# BUCK_SCHEM.net
KiCad netlist of a schematic drawn in Altium Designer
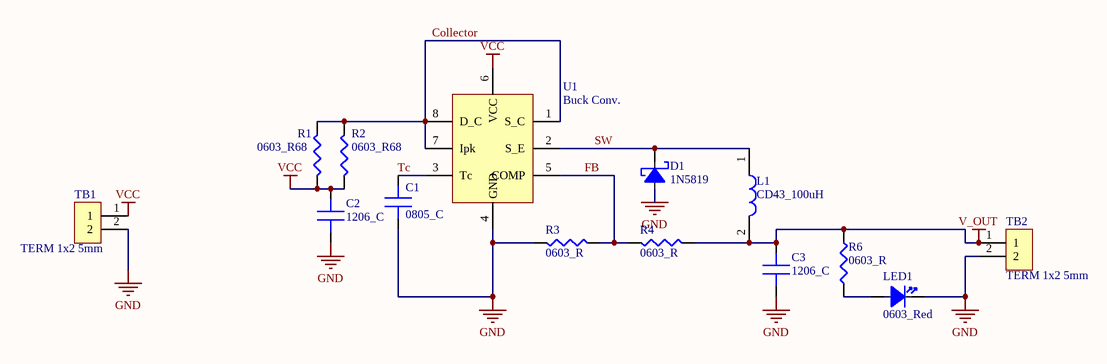
[diagram p0: BUCK_SCHEM.SchDoc]

(export (version "E")
  (design (tool "Eeschema 10.0.6"))
  (components
    (comp (ref "C1")
      (value "0805_C")
      (footprint "C0805 - 0.1uf")
      (description "0805 Capacitor")
      (libsource (lib "TimerSMD_Components") (part "0805 Capacitor"))
    )
    (comp (ref "C2")
      (value "1206_C")
      (footprint "1206")
      (description "1206 Capacitor")
      (libsource (lib "TimerSMD_Components") (part "1206 Capacitor"))
    )
    (comp (ref "C3")
      (value "1206_C")
      (footprint "1206")
      (description "1206 Capacitor")
      (libsource (lib "TimerSMD_Components") (part "1206 Capacitor"))
    )
    (comp (ref "D1")
      (value "1N5819")
      (footprint "D0-214AC")
      (description "1N5819 SS14 SMA Schottky Barrier Diodes (SBD) 40V 550mV@1A 1A")
      (libsource (lib "TimerSMD_Components") (part "1N5819"))
    )
    (comp (ref "L1")
      (value "CD43_100uH")
      (footprint "CD43")
      (libsource (lib "TimerSMD_Components") (part "100uH 4.5x4x3.2mm"))
    )
    (comp (ref "LED1")
      (value "0603_Red")
      (footprint "0603_LED")
      (libsource (lib "TimerSMD_Components") (part "0603LED"))
    )
    (comp (ref "R1")
      (value "0603_R68")
      (footprint "0603_CAP")
      (libsource (lib "TimerSMD_Components") (part "0603 Resistor"))
    )
    (comp (ref "R2")
      (value "0603_R68")
      (footprint "0603_CAP")
      (libsource (lib "TimerSMD_Components") (part "0603 Resistor"))
    )
    (comp (ref "R3")
      (value "0603_R")
      (footprint "0603_CAP")
      (libsource (lib "TimerSMD_Components") (part "0603 Resistor"))
    )
    (comp (ref "R4")
      (value "0603_R")
      (footprint "0603_CAP")
      (libsource (lib "TimerSMD_Components") (part "0603 Resistor"))
    )
    (comp (ref "R6")
      (value "0603_R")
      (footprint "0603_CAP")
      (libsource (lib "TimerSMD_Components") (part "0603 Resistor"))
    )
    (comp (ref "TB1")
      (value "TERM 1x2 5mm")
      (footprint "Terminal_5mm")
      (fields (field (name "VOLTAGE") "300V"))
      (libsource (lib "TimerSMD_Components") (part "Terminal BLK Green"))
    )
    (comp (ref "TB2")
      (value "TERM 1x2 5mm")
      (footprint "Terminal_5mm")
      (fields (field (name "VOLTAGE") "300V"))
      (libsource (lib "") (part "Terminal BLK Green_1"))
    )
    (comp (ref "U1")
      (value "Buck Conv.")
      (footprint "SOP8")
      (libsource (lib "TimerSMD_Components") (part "MC33063A"))
    )
  )
  (nets
    (net (code "1") (name "/Collector") (class "Default")
      (node (ref "R1") (pin "2") (pinfunction "2_2") (pintype "passive"))
      (node (ref "R2") (pin "2") (pinfunction "2_2") (pintype "passive"))
      (node (ref "U1") (pin "1") (pinfunction "S_C_1") (pintype "passive"))
      (node (ref "U1") (pin "7") (pinfunction "Ipk_7") (pintype "passive"))
      (node (ref "U1") (pin "8") (pinfunction "D_C_8") (pintype "passive"))
    )
    (net (code "2") (name "/FB") (class "Default")
      (node (ref "R3") (pin "2") (pinfunction "2_2") (pintype "passive"))
      (node (ref "R4") (pin "1") (pinfunction "1_1") (pintype "passive"))
      (node (ref "U1") (pin "5") (pinfunction "COMP_5") (pintype "passive"))
    )
    (net (code "3") (name "/SW") (class "Default")
      (node (ref "D1") (pin "K") (pinfunction "Cathode_K") (pintype "passive"))
      (node (ref "L1") (pin "1") (pinfunction "1_1") (pintype "passive"))
      (node (ref "U1") (pin "2") (pinfunction "S_E_2") (pintype "passive"))
    )
    (net (code "4") (name "/Tc") (class "Default")
      (node (ref "C1") (pin "2") (pinfunction "2_2") (pintype "passive"))
      (node (ref "U1") (pin "3") (pinfunction "Tc_3") (pintype "passive"))
    )
    (net (code "5") (name "GND") (class "Default")
      (node (ref "C1") (pin "1") (pinfunction "1_1") (pintype "passive"))
      (node (ref "C2") (pin "1") (pinfunction "1_1") (pintype "passive"))
      (node (ref "C3") (pin "1") (pinfunction "1_1") (pintype "passive"))
      (node (ref "D1") (pin "A") (pinfunction "Anode_A") (pintype "passive"))
      (node (ref "LED1") (pin "2") (pinfunction "Cathode_2") (pintype "passive"))
      (node (ref "R3") (pin "1") (pinfunction "1_1") (pintype "passive"))
      (node (ref "TB1") (pin "2") (pinfunction "2_2") (pintype "passive"))
      (node (ref "TB2") (pin "2") (pinfunction "2_2") (pintype "passive"))
      (node (ref "U1") (pin "4") (pinfunction "GND_4") (pintype "passive"))
    )
    (net (code "6") (name "Net-(LED1-Anode)") (class "Default")
      (node (ref "LED1") (pin "1") (pinfunction "Anode_1") (pintype "passive"))
      (node (ref "R6") (pin "1") (pinfunction "1_1") (pintype "passive"))
    )
    (net (code "7") (name "VCC") (class "Default")
      (node (ref "C2") (pin "2") (pinfunction "2_2") (pintype "passive"))
      (node (ref "R1") (pin "1") (pinfunction "1_1") (pintype "passive"))
      (node (ref "R2") (pin "1") (pinfunction "1_1") (pintype "passive"))
      (node (ref "TB1") (pin "1") (pinfunction "1_1") (pintype "passive"))
      (node (ref "U1") (pin "6") (pinfunction "VCC_6") (pintype "passive"))
    )
    (net (code "8") (name "V_OUT") (class "Default")
      (node (ref "C3") (pin "2") (pinfunction "2_2") (pintype "passive"))
      (node (ref "L1") (pin "2") (pinfunction "2_2") (pintype "passive"))
      (node (ref "R4") (pin "2") (pinfunction "2_2") (pintype "passive"))
      (node (ref "R6") (pin "2") (pinfunction "2_2") (pintype "passive"))
      (node (ref "TB2") (pin "1") (pinfunction "1_1") (pintype "passive"))
    )
  )
)
